# SAMD21_Base_schematic.net
KiCad netlist of a schematic drawn in Altium Designer
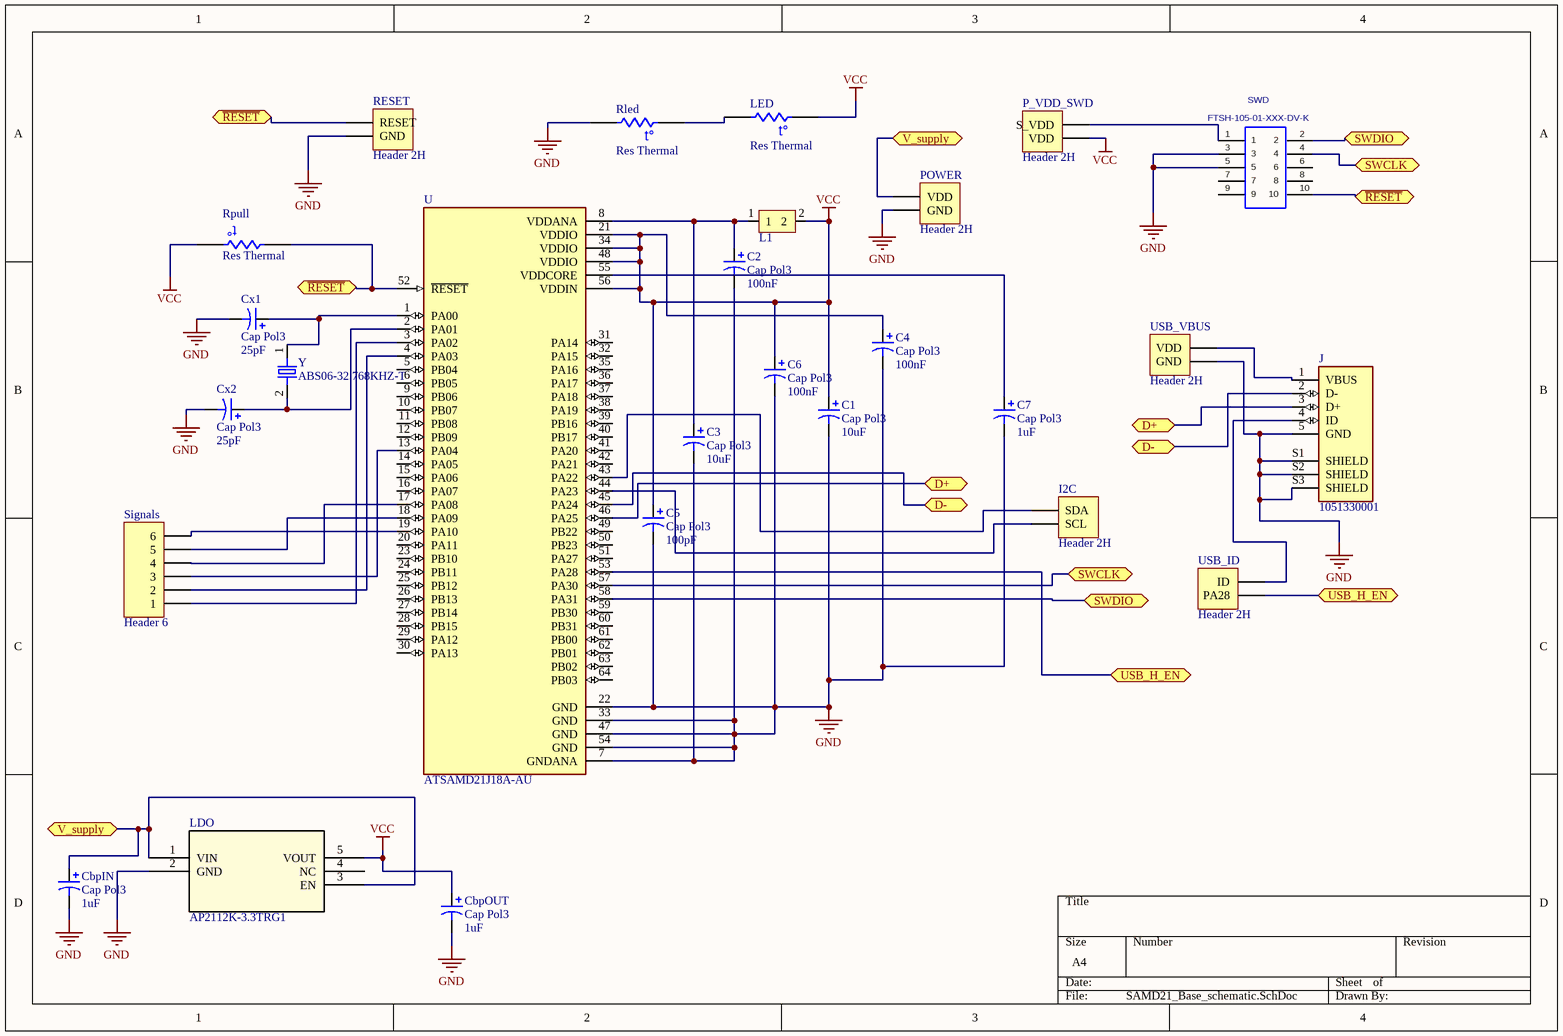
[diagram p0: SAMD21_Base_schematic.SchDoc]

(export (version "E")
  (design (tool "Eeschema 10.0.6"))
  (components
    (comp (ref "C1")
      (value "Cap Pol3")
      (footprint "C0805")
      (description "Polarized Capacitor (Surface Mount)")
      (fields (field (name "ALTIUM_VALUE") "10uF") (field (name "PUBLISHER") "Altium Limited"))
      (libsource (lib "Miscellaneous Devices") (part "Cap Pol3"))
    )
    (comp (ref "C2")
      (value "Cap Pol3")
      (footprint "C0805")
      (description "Polarized Capacitor (Surface Mount)")
      (fields (field (name "ALTIUM_VALUE") "100nF") (field (name "PUBLISHER") "Altium Limited"))
      (libsource (lib "Miscellaneous Devices") (part "Cap Pol3"))
    )
    (comp (ref "C3")
      (value "Cap Pol3")
      (footprint "C0805")
      (description "Polarized Capacitor (Surface Mount)")
      (fields (field (name "ALTIUM_VALUE") "10uF") (field (name "PUBLISHER") "Altium Limited"))
      (libsource (lib "Miscellaneous Devices") (part "Cap Pol3"))
    )
    (comp (ref "C4")
      (value "Cap Pol3")
      (footprint "C0805")
      (description "Polarized Capacitor (Surface Mount)")
      (fields (field (name "ALTIUM_VALUE") "100nF") (field (name "PUBLISHER") "Altium Limited"))
      (libsource (lib "Miscellaneous Devices") (part "Cap Pol3"))
    )
    (comp (ref "C5")
      (value "Cap Pol3")
      (footprint "C0805")
      (description "Polarized Capacitor (Surface Mount)")
      (fields (field (name "ALTIUM_VALUE") "100pF") (field (name "PUBLISHER") "Altium Limited"))
      (libsource (lib "Miscellaneous Devices") (part "Cap Pol3"))
    )
    (comp (ref "C6")
      (value "Cap Pol3")
      (footprint "C0805")
      (description "Polarized Capacitor (Surface Mount)")
      (fields (field (name "ALTIUM_VALUE") "100nF") (field (name "PUBLISHER") "Altium Limited"))
      (libsource (lib "Miscellaneous Devices") (part "Cap Pol3"))
    )
    (comp (ref "C7")
      (value "Cap Pol3")
      (footprint "C0805")
      (description "Polarized Capacitor (Surface Mount)")
      (fields (field (name "ALTIUM_VALUE") "1uF") (field (name "PUBLISHER") "Altium Limited"))
      (libsource (lib "Miscellaneous Devices") (part "Cap Pol3"))
    )
    (comp (ref "CbpIN")
      (value "Cap Pol3")
      (footprint "C0805")
      (description "Polarized Capacitor (Surface Mount)")
      (fields (field (name "ALTIUM_VALUE") "1uF") (field (name "PUBLISHER") "Altium Limited"))
      (libsource (lib "Miscellaneous Devices") (part "Cap Pol3"))
    )
    (comp (ref "CbpOUT")
      (value "Cap Pol3")
      (footprint "C0805")
      (description "Polarized Capacitor (Surface Mount)")
      (fields (field (name "ALTIUM_VALUE") "1uF") (field (name "PUBLISHER") "Altium Limited"))
      (libsource (lib "Miscellaneous Devices") (part "Cap Pol3"))
    )
    (comp (ref "Cx1")
      (value "Cap Pol3")
      (footprint "C0805")
      (description "Polarized Capacitor (Surface Mount)")
      (fields (field (name "ALTIUM_VALUE") "25pF") (field (name "PUBLISHER") "Altium Limited"))
      (libsource (lib "Miscellaneous Devices") (part "Cap Pol3"))
    )
    (comp (ref "Cx2")
      (value "Cap Pol3")
      (footprint "C0805")
      (description "Polarized Capacitor (Surface Mount)")
      (fields (field (name "ALTIUM_VALUE") "25pF") (field (name "PUBLISHER") "Altium Limited"))
      (libsource (lib "Miscellaneous Devices") (part "Cap Pol3"))
    )
    (comp (ref "I2C")
      (value "Header 2H")
      (footprint "HDR1X2H")
      (description "Header, 2-Pin, Right Angle")
      (fields (field (name "PUBLISHER") "Altium Limited"))
      (libsource (lib "Miscellaneous Connectors") (part "Header 2H"))
    )
    (comp (ref "J")
      (value "1051330001")
      (footprint "MOLEX_1051330001")
      (description "USB Connectors MICRO USB B RECPT VERTICAL")
      (fields (field (name "MP") "105133-0001") (field (name "MF") "Molex"))
      (libsource (lib "1051330001") (part "1051330001"))
    )
    (comp (ref "L1")
      (value "SRP4012TA-100M")
      (footprint "Inductor")
      (description "Inductor")
      (libsource (lib "SRP4012TA") (part "SRP4012TA-100M"))
    )
    (comp (ref "LDO")
      (value "AP2112K-3.3TRG1")
      (footprint "SOT_RG1_DIO")
      (description "No Description Available")
      (fields (field (name "COPYRIGHT") "Copyright (C) 2018 Accelerated Designs. All rights reserved"))
      (libsource (lib "2020-09-03_20-14-04") (part "AP2112K-3.3TRG1"))
    )
    (comp (ref "LED")
      (value "Res Thermal")
      (footprint "6-0805_N")
      (description "Thermistor")
      (fields (field (name "PUBLISHER") "Altium Limited"))
      (libsource (lib "Miscellaneous Devices") (part "Res Thermal"))
    )
    (comp (ref "POWER")
      (value "Header 2H")
      (footprint "HDR1X2H")
      (description "Header, 2-Pin, Right Angle")
      (fields (field (name "PUBLISHER") "Altium Limited"))
      (libsource (lib "Miscellaneous Connectors") (part "Header 2H"))
    )
    (comp (ref "P_VDD_SWD")
      (value "Header 2H")
      (footprint "HDR1X2H")
      (description "Header, 2-Pin, Right Angle")
      (fields (field (name "PUBLISHER") "Altium Limited"))
      (libsource (lib "") (part "Header 2H_1"))
    )
    (comp (ref "RESET")
      (value "Header 2H")
      (footprint "HDR1X2H")
      (description "Header, 2-Pin, Right Angle")
      (fields (field (name "PUBLISHER") "Altium Limited"))
      (libsource (lib "Miscellaneous Connectors") (part "Header 2H"))
    )
    (comp (ref "Rled")
      (value "Res Thermal")
      (footprint "6-0805_N")
      (description "Thermistor")
      (fields (field (name "PUBLISHER") "Altium Limited"))
      (libsource (lib "Miscellaneous Devices") (part "Res Thermal"))
    )
    (comp (ref "Rpull")
      (value "Res Thermal")
      (footprint "6-0805_N")
      (description "Thermistor")
      (fields (field (name "PUBLISHER") "Altium Limited"))
      (libsource (lib "Miscellaneous Devices") (part "Res Thermal"))
    )
    (comp (ref "Signals")
      (value "Header 6")
      (footprint "HDR1X6")
      (description "Header, 6-Pin")
      (fields (field (name "PUBLISHER") "Altium Limited"))
      (libsource (lib "Miscellaneous Connectors") (part "Header 6"))
    )
    (comp (ref "SWD")
      (value "FTSH-105-01-XXX-DV-K")
      (footprint "FTSH-105-01-XXX-DV-K")
      (description "TERMINAL STRIP, .050\"(1.27mm) PITCH, 10 PINS, KEYED")
      (fields (field (name "MANUFACTURER") "SAMTEC") (field (name "CREATED") "November 30, 2016 - Wendy Xin"))
      (libsource (lib "FTSH-105-01-XXX-DV-K--Symbol-Altium-44987") (part "FTSH-105-01-XXX-DV-K"))
    )
    (comp (ref "U")
      (value "ATSAMD21J18A-AU")
      (footprint "QFP80P1600X1600X120-64N")
      (description "ARMÂ® CortexÂ®-M0+ SAM D21J Microcontroller IC 32-Bit 48MHz 256KB _256K x 8_ FLASH 64-TQFP _10x10_")
      (fields (field (name "MF") "Microchip"))
      (libsource (lib "ATSAMD21J18A-AU") (part "ATSAMD21J18A-AU"))
    )
    (comp (ref "USB_ID")
      (value "Header 2H")
      (footprint "HDR1X2H")
      (description "Header, 2-Pin, Right Angle")
      (fields (field (name "PUBLISHER") "Altium Limited"))
      (libsource (lib "") (part "Header 2H_2"))
    )
    (comp (ref "USB_VBUS")
      (value "Header 2H")
      (footprint "HDR1X2H")
      (description "Header, 2-Pin, Right Angle")
      (fields (field (name "PUBLISHER") "Altium Limited"))
      (libsource (lib "") (part "Header 2H_3"))
    )
    (comp (ref "Y")
      (value "ABS06-32.768KHZ-T")
      (footprint "XTAL_ABS06-32.768KHZ-T")
      (description "32.768kHz Â±20ppm Crystal 12.5pF 90 kOhms 2-SMD, No Lead")
      (fields (field (name "MF") "Abracon"))
      (libsource (lib "ABS06-32.768KHZ-T") (part "ABS06-32.768KHZ-T"))
    )
  )
  (nets
    (net (code "1") (name "/D+") (class "Default")
      (node (ref "J") (pin "3") (pinfunction "D+_3") (pintype "bidirectional"))
      (node (ref "U") (pin "46") (pinfunction "PA25_46") (pintype "bidirectional"))
    )
    (net (code "2") (name "/D-") (class "Default")
      (node (ref "J") (pin "2") (pinfunction "D-_2") (pintype "bidirectional"))
      (node (ref "U") (pin "45") (pinfunction "PA24_45") (pintype "bidirectional"))
    )
    (net (code "3") (name "/SWCLK") (class "Default")
      (node (ref "SWD") (pin "4") (pinfunction "4_4") (pintype "passive"))
      (node (ref "U") (pin "57") (pinfunction "PA30_57") (pintype "bidirectional"))
    )
    (net (code "4") (name "/SWDIO") (class "Default")
      (node (ref "SWD") (pin "2") (pinfunction "2_2") (pintype "passive"))
      (node (ref "U") (pin "58") (pinfunction "PA31_58") (pintype "bidirectional"))
    )
    (net (code "5") (name "/USB_H_EN") (class "Default")
      (node (ref "U") (pin "53") (pinfunction "PA28_53") (pintype "bidirectional"))
      (node (ref "USB_ID") (pin "1") (pinfunction "PA28_1") (pintype "passive"))
    )
    (net (code "6") (name "/V_supply") (class "Default")
      (node (ref "CbpIN") (pin "1") (pinfunction "1_1") (pintype "passive"))
      (node (ref "LDO") (pin "1") (pinfunction "VIN_1") (pintype "passive"))
      (node (ref "LDO") (pin "3") (pinfunction "EN_3") (pintype "passive"))
      (node (ref "POWER") (pin "1") (pinfunction "SDA_1") (pintype "passive"))
    )
    (net (code "7") (name "/~{RESET}") (class "Default")
      (node (ref "RESET") (pin "1") (pinfunction "SDA_1") (pintype "passive"))
      (node (ref "Rpull") (pin "2") (pinfunction "2_2") (pintype "passive"))
      (node (ref "SWD") (pin "10") (pinfunction "10_10") (pintype "passive"))
      (node (ref "U") (pin "52") (pinfunction "~{RESET}_52") (pintype "input"))
    )
    (net (code "8") (name "GND") (class "Default")
      (node (ref "C1") (pin "2") (pinfunction "2_2") (pintype "passive"))
      (node (ref "C2") (pin "2") (pinfunction "2_2") (pintype "passive"))
      (node (ref "C3") (pin "2") (pinfunction "2_2") (pintype "passive"))
      (node (ref "C4") (pin "2") (pinfunction "2_2") (pintype "passive"))
      (node (ref "C5") (pin "2") (pinfunction "2_2") (pintype "passive"))
      (node (ref "C6") (pin "2") (pinfunction "2_2") (pintype "passive"))
      (node (ref "C7") (pin "2") (pinfunction "2_2") (pintype "passive"))
      (node (ref "CbpIN") (pin "2") (pinfunction "2_2") (pintype "passive"))
      (node (ref "CbpOUT") (pin "2") (pinfunction "2_2") (pintype "passive"))
      (node (ref "Cx1") (pin "2") (pinfunction "2_2") (pintype "passive"))
      (node (ref "Cx2") (pin "2") (pinfunction "2_2") (pintype "passive"))
      (node (ref "J") (pin "5") (pinfunction "GND_5") (pintype "power_in"))
      (node (ref "J") (pin "S1") (pinfunction "SHIELD_S1") (pintype "passive"))
      (node (ref "J") (pin "S2") (pinfunction "SHIELD_S2") (pintype "passive"))
      (node (ref "J") (pin "S3") (pinfunction "SHIELD_S3") (pintype "passive"))
      (node (ref "LDO") (pin "2") (pinfunction "GND_2") (pintype "passive"))
      (node (ref "POWER") (pin "2") (pinfunction "SCL_2") (pintype "passive"))
      (node (ref "RESET") (pin "2") (pinfunction "SCL_2") (pintype "passive"))
      (node (ref "Rled") (pin "2") (pinfunction "2_2") (pintype "passive"))
      (node (ref "SWD") (pin "3") (pinfunction "3_3") (pintype "passive"))
      (node (ref "SWD") (pin "5") (pinfunction "5_5") (pintype "passive"))
      (node (ref "U") (pin "22") (pinfunction "GND_22") (pintype "power_in"))
      (node (ref "U") (pin "33") (pinfunction "GND_33") (pintype "power_in"))
      (node (ref "U") (pin "47") (pinfunction "GND_47") (pintype "power_in"))
      (node (ref "U") (pin "54") (pinfunction "GND_54") (pintype "power_in"))
      (node (ref "U") (pin "7") (pinfunction "GNDANA_7") (pintype "power_in"))
      (node (ref "USB_VBUS") (pin "1") (pinfunction "GND_1") (pintype "passive"))
    )
    (net (code "9") (name "Net-(I2C-SCL)") (class "Default")
      (node (ref "I2C") (pin "2") (pinfunction "SCL_2") (pintype "passive"))
      (node (ref "U") (pin "44") (pinfunction "PA23_44") (pintype "bidirectional"))
    )
    (net (code "10") (name "Net-(I2C-SDA)") (class "Default")
      (node (ref "I2C") (pin "1") (pinfunction "SDA_1") (pintype "passive"))
      (node (ref "U") (pin "43") (pinfunction "PA22_43") (pintype "bidirectional"))
    )
    (net (code "11") (name "Net-(J-ID)") (class "Default")
      (node (ref "J") (pin "4") (pinfunction "ID_4") (pintype "bidirectional"))
      (node (ref "USB_ID") (pin "2") (pinfunction "ID_2") (pintype "passive"))
    )
    (net (code "12") (name "Net-(J-VBUS)") (class "Default")
      (node (ref "J") (pin "1") (pinfunction "VBUS_1") (pintype "power_in"))
      (node (ref "USB_VBUS") (pin "2") (pinfunction "VDD_2") (pintype "passive"))
    )
    (net (code "13") (name "Net-(LED-Pad2)") (class "Default")
      (node (ref "LED") (pin "2") (pinfunction "2_2") (pintype "passive"))
      (node (ref "Rled") (pin "1") (pinfunction "1_1") (pintype "passive"))
    )
    (net (code "14") (name "Net-(P_VDD_SWD-S_VDD)") (class "Default")
      (node (ref "P_VDD_SWD") (pin "2") (pinfunction "S_VDD_2") (pintype "passive"))
      (node (ref "SWD") (pin "1") (pinfunction "1_1") (pintype "passive"))
    )
    (net (code "15") (name "Net-(U-PA00)") (class "Default")
      (node (ref "Cx1") (pin "1") (pinfunction "1_1") (pintype "passive"))
      (node (ref "U") (pin "1") (pinfunction "PA00_1") (pintype "bidirectional"))
      (node (ref "Y") (pin "1") (pinfunction "1_1") (pintype "passive"))
    )
    (net (code "16") (name "Net-(U-PA01)") (class "Default")
      (node (ref "Cx2") (pin "1") (pinfunction "1_1") (pintype "passive"))
      (node (ref "U") (pin "2") (pinfunction "PA01_2") (pintype "bidirectional"))
      (node (ref "Y") (pin "2") (pinfunction "2_2") (pintype "passive"))
    )
    (net (code "17") (name "Net-(U-PA02)") (class "Default")
      (node (ref "Signals") (pin "1") (pinfunction "1_1") (pintype "passive"))
      (node (ref "U") (pin "3") (pinfunction "PA02_3") (pintype "bidirectional"))
    )
    (net (code "18") (name "Net-(U-PA03)") (class "Default")
      (node (ref "Signals") (pin "2") (pinfunction "2_2") (pintype "passive"))
      (node (ref "U") (pin "4") (pinfunction "PA03_4") (pintype "bidirectional"))
    )
    (net (code "19") (name "Net-(U-PA04)") (class "Default")
      (node (ref "Signals") (pin "3") (pinfunction "3_3") (pintype "passive"))
      (node (ref "U") (pin "13") (pinfunction "PA04_13") (pintype "bidirectional"))
    )
    (net (code "20") (name "Net-(U-PA08)") (class "Default")
      (node (ref "Signals") (pin "4") (pinfunction "4_4") (pintype "passive"))
      (node (ref "U") (pin "17") (pinfunction "PA08_17") (pintype "bidirectional"))
    )
    (net (code "21") (name "Net-(U-PA09)") (class "Default")
      (node (ref "Signals") (pin "5") (pinfunction "5_5") (pintype "passive"))
      (node (ref "U") (pin "18") (pinfunction "PA09_18") (pintype "bidirectional"))
    )
    (net (code "22") (name "Net-(U-PA10)") (class "Default")
      (node (ref "Signals") (pin "6") (pinfunction "6_6") (pintype "passive"))
      (node (ref "U") (pin "19") (pinfunction "PA10_19") (pintype "bidirectional"))
    )
    (net (code "23") (name "Net-(U-VDDANA)") (class "Default")
      (node (ref "C2") (pin "1") (pinfunction "1_1") (pintype "passive"))
      (node (ref "C3") (pin "1") (pinfunction "1_1") (pintype "passive"))
      (node (ref "L1") (pin "1") (pinfunction "1_1") (pintype "passive"))
      (node (ref "U") (pin "8") (pinfunction "VDDANA_8") (pintype "power_in"))
    )
    (net (code "24") (name "Net-(U-VDDCORE)") (class "Default")
      (node (ref "C7") (pin "1") (pinfunction "1_1") (pintype "passive"))
      (node (ref "U") (pin "55") (pinfunction "VDDCORE_55") (pintype "power_in"))
    )
    (net (code "25") (name "VCC") (class "Default")
      (node (ref "C1") (pin "1") (pinfunction "1_1") (pintype "passive"))
      (node (ref "C4") (pin "1") (pinfunction "1_1") (pintype "passive"))
      (node (ref "C5") (pin "1") (pinfunction "1_1") (pintype "passive"))
      (node (ref "C6") (pin "1") (pinfunction "1_1") (pintype "passive"))
      (node (ref "CbpOUT") (pin "1") (pinfunction "1_1") (pintype "passive"))
      (node (ref "L1") (pin "2") (pinfunction "2_2") (pintype "passive"))
      (node (ref "LDO") (pin "5") (pinfunction "VOUT_5") (pintype "passive"))
      (node (ref "LED") (pin "1") (pinfunction "1_1") (pintype "passive"))
      (node (ref "P_VDD_SWD") (pin "1") (pinfunction "VDD_1") (pintype "passive"))
      (node (ref "Rpull") (pin "1") (pinfunction "1_1") (pintype "passive"))
      (node (ref "U") (pin "21") (pinfunction "VDDIO_21") (pintype "power_in"))
      (node (ref "U") (pin "34") (pinfunction "VDDIO_34") (pintype "power_in"))
      (node (ref "U") (pin "48") (pinfunction "VDDIO_48") (pintype "power_in"))
      (node (ref "U") (pin "56") (pinfunction "VDDIN_56") (pintype "power_in"))
    )
    (net (code "26") (name "unconnected-(LDO-NC-Pad4)") (class "Default")
      (node (ref "LDO") (pin "4") (pinfunction "NC_4") (pintype "passive"))
    )
    (net (code "27") (name "unconnected-(SWD-Pad6)") (class "Default")
      (node (ref "SWD") (pin "6") (pinfunction "6_6") (pintype "passive"))
    )
    (net (code "28") (name "unconnected-(SWD-Pad7)") (class "Default")
      (node (ref "SWD") (pin "7") (pinfunction "7_7") (pintype "passive"))
    )
    (net (code "29") (name "unconnected-(SWD-Pad8)") (class "Default")
      (node (ref "SWD") (pin "8") (pinfunction "8_8") (pintype "passive"))
    )
    (net (code "30") (name "unconnected-(SWD-Pad9)") (class "Default")
      (node (ref "SWD") (pin "9") (pinfunction "9_9") (pintype "passive"))
    )
    (net (code "31") (name "unconnected-(U-PA05-Pad14)") (class "Default")
      (node (ref "U") (pin "14") (pinfunction "PA05_14") (pintype "bidirectional"))
    )
    (net (code "32") (name "unconnected-(U-PA06-Pad15)") (class "Default")
      (node (ref "U") (pin "15") (pinfunction "PA06_15") (pintype "bidirectional"))
    )
    (net (code "33") (name "unconnected-(U-PA07-Pad16)") (class "Default")
      (node (ref "U") (pin "16") (pinfunction "PA07_16") (pintype "bidirectional"))
    )
    (net (code "34") (name "unconnected-(U-PA11-Pad20)") (class "Default")
      (node (ref "U") (pin "20") (pinfunction "PA11_20") (pintype "bidirectional"))
    )
    (net (code "35") (name "unconnected-(U-PA12-Pad29)") (class "Default")
      (node (ref "U") (pin "29") (pinfunction "PA12_29") (pintype "bidirectional"))
    )
    (net (code "36") (name "unconnected-(U-PA13-Pad30)") (class "Default")
      (node (ref "U") (pin "30") (pinfunction "PA13_30") (pintype "bidirectional"))
    )
    (net (code "37") (name "unconnected-(U-PA14-Pad31)") (class "Default")
      (node (ref "U") (pin "31") (pinfunction "PA14_31") (pintype "bidirectional"))
    )
    (net (code "38") (name "unconnected-(U-PA15-Pad32)") (class "Default")
      (node (ref "U") (pin "32") (pinfunction "PA15_32") (pintype "bidirectional"))
    )
    (net (code "39") (name "unconnected-(U-PA16-Pad35)") (class "Default")
      (node (ref "U") (pin "35") (pinfunction "PA16_35") (pintype "bidirectional"))
    )
    (net (code "40") (name "unconnected-(U-PA17-Pad36)") (class "Default")
      (node (ref "U") (pin "36") (pinfunction "PA17_36") (pintype "bidirectional"))
    )
    (net (code "41") (name "unconnected-(U-PA18-Pad37)") (class "Default")
      (node (ref "U") (pin "37") (pinfunction "PA18_37") (pintype "bidirectional"))
    )
    (net (code "42") (name "unconnected-(U-PA19-Pad38)") (class "Default")
      (node (ref "U") (pin "38") (pinfunction "PA19_38") (pintype "bidirectional"))
    )
    (net (code "43") (name "unconnected-(U-PA20-Pad41)") (class "Default")
      (node (ref "U") (pin "41") (pinfunction "PA20_41") (pintype "bidirectional"))
    )
    (net (code "44") (name "unconnected-(U-PA21-Pad42)") (class "Default")
      (node (ref "U") (pin "42") (pinfunction "PA21_42") (pintype "bidirectional"))
    )
    (net (code "45") (name "unconnected-(U-PA27-Pad51)") (class "Default")
      (node (ref "U") (pin "51") (pinfunction "PA27_51") (pintype "bidirectional"))
    )
    (net (code "46") (name "unconnected-(U-PB00-Pad61)") (class "Default")
      (node (ref "U") (pin "61") (pinfunction "PB00_61") (pintype "bidirectional"))
    )
    (net (code "47") (name "unconnected-(U-PB01-Pad62)") (class "Default")
      (node (ref "U") (pin "62") (pinfunction "PB01_62") (pintype "bidirectional"))
    )
    (net (code "48") (name "unconnected-(U-PB02-Pad63)") (class "Default")
      (node (ref "U") (pin "63") (pinfunction "PB02_63") (pintype "bidirectional"))
    )
    (net (code "49") (name "unconnected-(U-PB03-Pad64)") (class "Default")
      (node (ref "U") (pin "64") (pinfunction "PB03_64") (pintype "bidirectional"))
    )
    (net (code "50") (name "unconnected-(U-PB04-Pad5)") (class "Default")
      (node (ref "U") (pin "5") (pinfunction "PB04_5") (pintype "bidirectional"))
    )
    (net (code "51") (name "unconnected-(U-PB05-Pad6)") (class "Default")
      (node (ref "U") (pin "6") (pinfunction "PB05_6") (pintype "bidirectional"))
    )
    (net (code "52") (name "unconnected-(U-PB06-Pad9)") (class "Default")
      (node (ref "U") (pin "9") (pinfunction "PB06_9") (pintype "bidirectional"))
    )
    (net (code "53") (name "unconnected-(U-PB07-Pad10)") (class "Default")
      (node (ref "U") (pin "10") (pinfunction "PB07_10") (pintype "bidirectional"))
    )
    (net (code "54") (name "unconnected-(U-PB08-Pad11)") (class "Default")
      (node (ref "U") (pin "11") (pinfunction "PB08_11") (pintype "bidirectional"))
    )
    (net (code "55") (name "unconnected-(U-PB09-Pad12)") (class "Default")
      (node (ref "U") (pin "12") (pinfunction "PB09_12") (pintype "bidirectional"))
    )
    (net (code "56") (name "unconnected-(U-PB10-Pad23)") (class "Default")
      (node (ref "U") (pin "23") (pinfunction "PB10_23") (pintype "bidirectional"))
    )
    (net (code "57") (name "unconnected-(U-PB11-Pad24)") (class "Default")
      (node (ref "U") (pin "24") (pinfunction "PB11_24") (pintype "bidirectional"))
    )
    (net (code "58") (name "unconnected-(U-PB12-Pad25)") (class "Default")
      (node (ref "U") (pin "25") (pinfunction "PB12_25") (pintype "bidirectional"))
    )
    (net (code "59") (name "unconnected-(U-PB13-Pad26)") (class "Default")
      (node (ref "U") (pin "26") (pinfunction "PB13_26") (pintype "bidirectional"))
    )
    (net (code "60") (name "unconnected-(U-PB14-Pad27)") (class "Default")
      (node (ref "U") (pin "27") (pinfunction "PB14_27") (pintype "bidirectional"))
    )
    (net (code "61") (name "unconnected-(U-PB15-Pad28)") (class "Default")
      (node (ref "U") (pin "28") (pinfunction "PB15_28") (pintype "bidirectional"))
    )
    (net (code "62") (name "unconnected-(U-PB16-Pad39)") (class "Default")
      (node (ref "U") (pin "39") (pinfunction "PB16_39") (pintype "bidirectional"))
    )
    (net (code "63") (name "unconnected-(U-PB17-Pad40)") (class "Default")
      (node (ref "U") (pin "40") (pinfunction "PB17_40") (pintype "bidirectional"))
    )
    (net (code "64") (name "unconnected-(U-PB22-Pad49)") (class "Default")
      (node (ref "U") (pin "49") (pinfunction "PB22_49") (pintype "bidirectional"))
    )
    (net (code "65") (name "unconnected-(U-PB23-Pad50)") (class "Default")
      (node (ref "U") (pin "50") (pinfunction "PB23_50") (pintype "bidirectional"))
    )
    (net (code "66") (name "unconnected-(U-PB30-Pad59)") (class "Default")
      (node (ref "U") (pin "59") (pinfunction "PB30_59") (pintype "bidirectional"))
    )
    (net (code "67") (name "unconnected-(U-PB31-Pad60)") (class "Default")
      (node (ref "U") (pin "60") (pinfunction "PB31_60") (pintype "bidirectional"))
    )
  )
)
